# BOWIE_IMU.net
KiCad netlist of a schematic drawn in Altium Designer
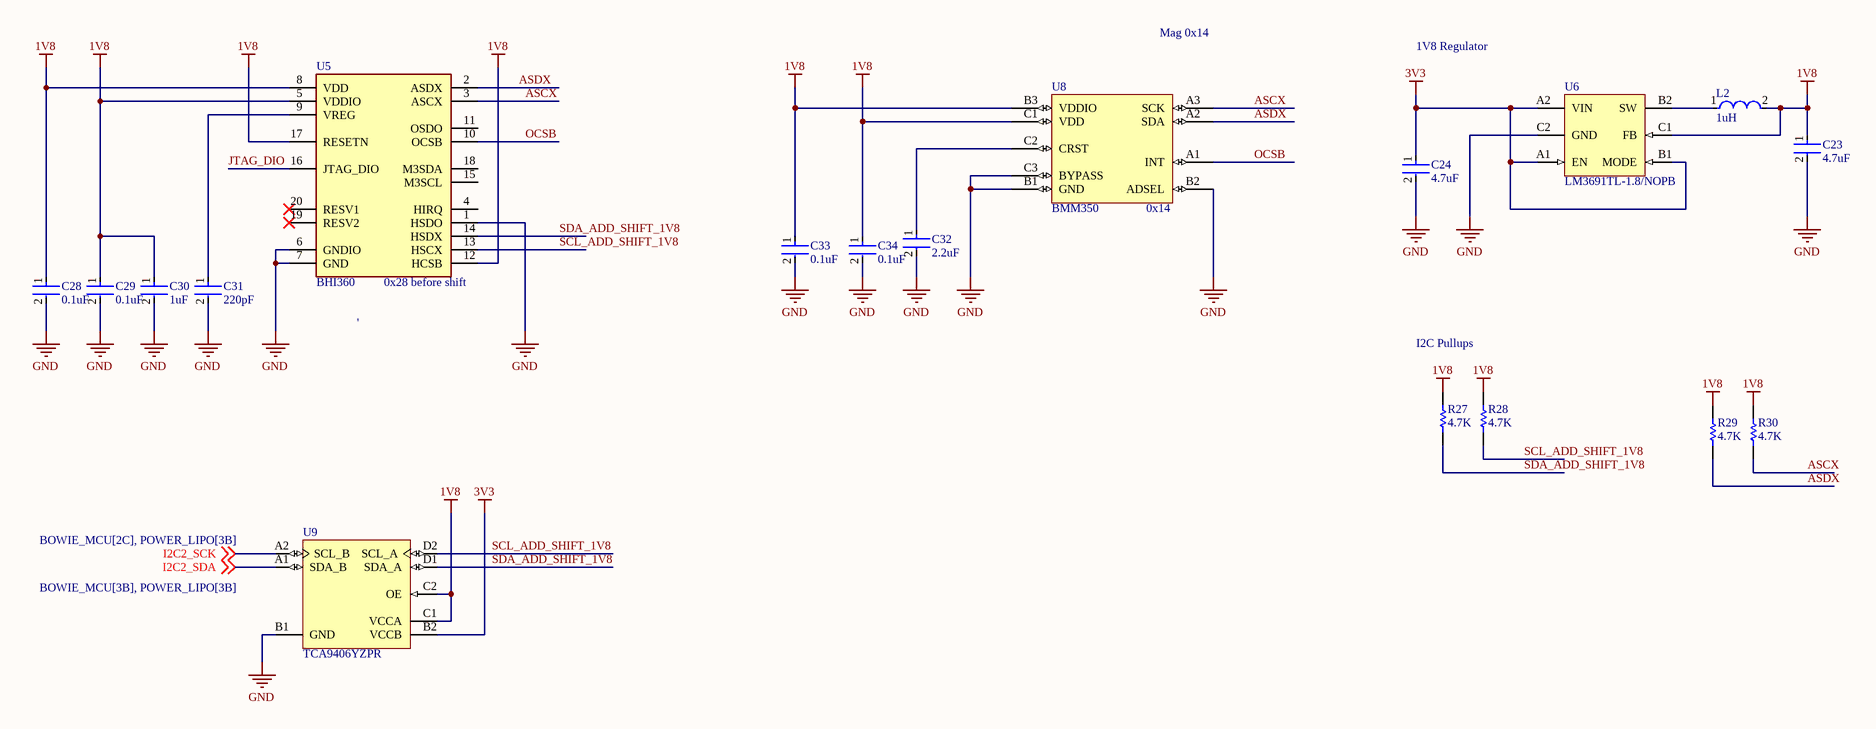
[diagram p0: BOWIE_IMU.SchDoc]

(export (version "E")
  (design (tool "Eeschema 10.0.6"))
  (components
    (comp (ref "C23")
      (value "4.7uF")
      (footprint "FP-CL828-IPC_C")
      (description "Cap Ceramic 4.7uF 10V X5R ±10% SMD 0402 +85°C Paper T/R")
      (fields (field (name "TOLERANCE") "10%"))
      (libsource (lib "Altium Content Vault") (part "b4654b650e69147ec39a6b967a45e02"))
    )
    (comp (ref "C24")
      (value "4.7uF")
      (footprint "FP-CL828-IPC_C")
      (description "Cap Ceramic 4.7uF 10V X5R ±10% SMD 0402 +85°C Paper T/R")
      (fields (field (name "TOLERANCE") "10%"))
      (libsource (lib "Altium Content Vault") (part "b4654b650e69147ec39a6b967a45e02"))
    )
    (comp (ref "C28")
      (value "0.1uF")
      (footprint "FP-GRM033-0_03-IPC_C")
      (description "Chip Multilayer Ceramic Capacitors for General Purpose, 0201, 0.10uF, X5R, 15%, 10%, 10V")
      (fields (field (name "TOLERANCE") "10%") (field (name "VOLTAGE") "10V"))
      (libsource (lib "Altium Content Vault") (part "b4654b650e69147ec39a6b967a45e02"))
    )
    (comp (ref "C29")
      (value "0.1uF")
      (footprint "FP-GRM033-0_03-IPC_C")
      (description "Chip Multilayer Ceramic Capacitors for General Purpose, 0201, 0.10uF, X5R, 15%, 10%, 10V")
      (fields (field (name "TOLERANCE") "10%") (field (name "VOLTAGE") "10V"))
      (libsource (lib "Altium Content Vault") (part "b4654b650e69147ec39a6b967a45e02"))
    )
    (comp (ref "C30")
      (value "1uF")
      (footprint "FP-GRM033-0_05-e01_0_2-IPC_C")
      (description "Chip Multilayer Ceramic Capacitors for General Purpose, 0201, 1.0uF, X5R, 15%, 20%, 4V")
      (fields (field (name "TOLERANCE") "20%"))
      (libsource (lib "Altium Content Vault") (part "02cd4be3c70576c341d710602a673aa"))
    )
    (comp (ref "C31")
      (value "220pF")
      (footprint "FP-GRM033-0_03-IPC_C")
      (description "Chip Multilayer Ceramic Capacitors for General Purpose, 0201, 220pF, X7R, 15%, 10%, 16V")
      (fields (field (name "TOLERANCE") "10%"))
      (libsource (lib "Altium Content Vault") (part "b4654b650e69147ec39a6b967a45e02"))
    )
    (comp (ref "C32")
      (value "2.2uF")
      (footprint "FP-GRM033-0_09-IPC_B")
      (description "Chip Multilayer Ceramic Capacitors for General Purpose, 0201, 2.2uF, X5R, 15%, 10%, 10V")
      (fields (field (name "TOLERANCE") "10%"))
      (libsource (lib "Altium Content Vault") (part "02cd4be3c70576c341d710602a673aa"))
    )
    (comp (ref "C33")
      (value "0.1uF")
      (footprint "FP-GRM033-0_03-IPC_C")
      (description "Chip Multilayer Ceramic Capacitors for General Purpose, 0201, 0.10uF, X5R, 15%, 10%, 10V")
      (fields (field (name "TOLERANCE") "10%") (field (name "VOLTAGE") "10V"))
      (libsource (lib "Altium Content Vault") (part "b4654b650e69147ec39a6b967a45e02"))
    )
    (comp (ref "C34")
      (value "0.1uF")
      (footprint "FP-GRM033-0_03-IPC_C")
      (description "Chip Multilayer Ceramic Capacitors for General Purpose, 0201, 0.10uF, X5R, 15%, 10%, 10V")
      (fields (field (name "TOLERANCE") "10%") (field (name "VOLTAGE") "10V"))
      (libsource (lib "Altium Content Vault") (part "b4654b650e69147ec39a6b967a45e02"))
    )
    (comp (ref "L2")
      (value "1uH")
      (footprint "FP-DFE18SAN_E0-MFG")
      (description "FIXED IND 1UH 1.6A 144 MOHM SMD")
      (fields (field (name "TOLERANCE") "20%"))
      (libsource (lib "Altium Content Vault") (part "725321dda6339637d4d059423bc1c3c"))
    )
    (comp (ref "R27")
      (value "4.7K")
      (footprint "RESC0603X26X15NL03T05")
      (fields (field (name "PART NUMBER") "ERJ-1GEF4701C") (field (name "MANUFACTURER") "Panasonic"))
      (libsource (lib "Altium Content Vault") (part "RES"))
    )
    (comp (ref "R28")
      (value "4.7K")
      (footprint "RESC0603X26X15NL03T05")
      (fields (field (name "PART NUMBER") "ERJ-1GEF4701C") (field (name "MANUFACTURER") "Panasonic"))
      (libsource (lib "Altium Content Vault") (part "RES"))
    )
    (comp (ref "R29")
      (value "4.7K")
      (footprint "RESC0603X26X15NL03T05")
      (fields (field (name "PART NUMBER") "ERJ-1GEF4701C") (field (name "MANUFACTURER") "Panasonic"))
      (libsource (lib "Altium Content Vault") (part "RES"))
    )
    (comp (ref "R30")
      (value "4.7K")
      (footprint "RESC0603X26X15NL03T05")
      (fields (field (name "PART NUMBER") "ERJ-1GEF4701C") (field (name "MANUFACTURER") "Panasonic"))
      (libsource (lib "Altium Content Vault") (part "RES"))
    )
    (comp (ref "U5")
      (value "BHI360")
      (footprint "BHI360")
      (fields (field (name "MOUSER PART NUMBER") "262-BHI360"))
      (libsource (lib "BHI360") (part "BHI360"))
    )
    (comp (ref "U6")
      (value "LM3691TL-1.8/NOPB")
      (footprint "YZR0006APAF")
      (fields (field (name "MANUFACTURER") "Texas Instruments"))
      (libsource (lib "Altium Content Vault") (part "PM-DCDC-LM3691-6"))
    )
    (comp (ref "U8") (value "BMM350") (footprint "BMM350") (libsource (lib "bmm350") (part "BMM350")))
    (comp (ref "U9")
      (value "TCA9406YZPR")
      (footprint "YZP0008ADAD")
      (fields (field (name "MANUFACTURER") "Texas Instruments"))
      (libsource (lib "Altium Content Vault") (part "TI-TCA9406-DSBGA_YZP-8"))
    )
  )
  (nets
    (net (code "1") (name "/ASCX") (class "Default")
      (node (ref "R30") (pin "1") (pinfunction "1_1") (pintype "passive"))
      (node (ref "U5") (pin "3") (pinfunction "ASCX_3") (pintype "passive"))
      (node (ref "U8") (pin "A3") (pinfunction "SCK_A3") (pintype "bidirectional"))
    )
    (net (code "2") (name "/ASDX") (class "Default")
      (node (ref "R29") (pin "1") (pinfunction "1_1") (pintype "passive"))
      (node (ref "U5") (pin "2") (pinfunction "ASDX_2") (pintype "passive"))
      (node (ref "U8") (pin "A2") (pinfunction "SDA_A2") (pintype "bidirectional"))
    )
    (net (code "3") (name "/JTAG_DIO") (class "Default")
      (node (ref "U5") (pin "16") (pinfunction "JTAG_DIO_16") (pintype "passive"))
    )
    (net (code "4") (name "/OCSB") (class "Default")
      (node (ref "U5") (pin "10") (pinfunction "OCSB_10") (pintype "passive"))
      (node (ref "U8") (pin "A1") (pinfunction "INT_A1") (pintype "bidirectional"))
    )
    (net (code "5") (name "/SCL_ADD_SHIFT_1V8") (class "Default")
      (node (ref "R28") (pin "1") (pinfunction "1_1") (pintype "passive"))
      (node (ref "U5") (pin "13") (pinfunction "HSCX_13") (pintype "passive"))
      (node (ref "U9") (pin "D2") (pinfunction "SCL_A_D2") (pintype "bidirectional"))
    )
    (net (code "6") (name "/SDA_ADD_SHIFT_1V8") (class "Default")
      (node (ref "R27") (pin "1") (pinfunction "1_1") (pintype "passive"))
      (node (ref "U5") (pin "14") (pinfunction "HSDX_14") (pintype "passive"))
      (node (ref "U9") (pin "D1") (pinfunction "SDA_A_D1") (pintype "bidirectional"))
    )
    (net (code "7") (name "1V8") (class "Default")
      (node (ref "C23") (pin "1") (pinfunction "1_1") (pintype "passive"))
      (node (ref "C28") (pin "1") (pinfunction "1_1") (pintype "passive"))
      (node (ref "C29") (pin "1") (pinfunction "1_1") (pintype "passive"))
      (node (ref "C30") (pin "1") (pinfunction "1_1") (pintype "passive"))
      (node (ref "C33") (pin "1") (pinfunction "1_1") (pintype "passive"))
      (node (ref "C34") (pin "1") (pinfunction "1_1") (pintype "passive"))
      (node (ref "L2") (pin "2") (pinfunction "2_2") (pintype "passive"))
      (node (ref "R27") (pin "2") (pinfunction "2_2") (pintype "passive"))
      (node (ref "R28") (pin "2") (pinfunction "2_2") (pintype "passive"))
      (node (ref "R29") (pin "2") (pinfunction "2_2") (pintype "passive"))
      (node (ref "R30") (pin "2") (pinfunction "2_2") (pintype "passive"))
      (node (ref "U5") (pin "12") (pinfunction "HCSB_12") (pintype "passive"))
      (node (ref "U5") (pin "17") (pinfunction "RESETN_17") (pintype "passive"))
      (node (ref "U5") (pin "5") (pinfunction "VDDIO_5") (pintype "passive"))
      (node (ref "U5") (pin "8") (pinfunction "VDD_8") (pintype "passive"))
      (node (ref "U6") (pin "C1") (pinfunction "FB_C1") (pintype "input"))
      (node (ref "U8") (pin "B3") (pinfunction "VDDIO_B3") (pintype "bidirectional"))
      (node (ref "U8") (pin "C1") (pinfunction "VDD_C1") (pintype "bidirectional"))
      (node (ref "U9") (pin "C1") (pinfunction "VCCA_C1") (pintype "power_in"))
      (node (ref "U9") (pin "C2") (pinfunction "OE_C2") (pintype "input"))
    )
    (net (code "8") (name "3V3") (class "Default")
      (node (ref "C24") (pin "1") (pinfunction "1_1") (pintype "passive"))
      (node (ref "U6") (pin "A1") (pinfunction "EN_A1") (pintype "input"))
      (node (ref "U6") (pin "A2") (pinfunction "VIN_A2") (pintype "power_in"))
      (node (ref "U6") (pin "B1") (pinfunction "MODE_B1") (pintype "input"))
      (node (ref "U9") (pin "B2") (pinfunction "VCCB_B2") (pintype "power_in"))
    )
    (net (code "9") (name "GND") (class "Default")
      (node (ref "C23") (pin "2") (pinfunction "2_2") (pintype "passive"))
      (node (ref "C24") (pin "2") (pinfunction "2_2") (pintype "passive"))
      (node (ref "C28") (pin "2") (pinfunction "2_2") (pintype "passive"))
      (node (ref "C29") (pin "2") (pinfunction "2_2") (pintype "passive"))
      (node (ref "C30") (pin "2") (pinfunction "2_2") (pintype "passive"))
      (node (ref "C31") (pin "2") (pinfunction "2_2") (pintype "passive"))
      (node (ref "C32") (pin "2") (pinfunction "2_2") (pintype "passive"))
      (node (ref "C33") (pin "2") (pinfunction "2_2") (pintype "passive"))
      (node (ref "C34") (pin "2") (pinfunction "2_2") (pintype "passive"))
      (node (ref "U5") (pin "1") (pinfunction "HSDO_1") (pintype "passive"))
      (node (ref "U5") (pin "6") (pinfunction "GNDIO_6") (pintype "passive"))
      (node (ref "U5") (pin "7") (pinfunction "GND_7") (pintype "passive"))
      (node (ref "U6") (pin "C2") (pinfunction "GND_C2") (pintype "power_in"))
      (node (ref "U8") (pin "B1") (pinfunction "GND_B1") (pintype "bidirectional"))
      (node (ref "U8") (pin "B2") (pinfunction "ADSEL_B2") (pintype "bidirectional"))
      (node (ref "U8") (pin "C3") (pinfunction "BYPASS_C3") (pintype "bidirectional"))
      (node (ref "U9") (pin "B1") (pinfunction "GND_B1") (pintype "power_in"))
    )
    (net (code "10") (name "I2C2_SCK") (class "Default")
      (node (ref "U9") (pin "A2") (pinfunction "SCL_B_A2") (pintype "bidirectional"))
    )
    (net (code "11") (name "I2C2_SDA") (class "Default")
      (node (ref "U9") (pin "A1") (pinfunction "SDA_B_A1") (pintype "bidirectional"))
    )
    (net (code "12") (name "Net-(U5-VREG)") (class "Default")
      (node (ref "C31") (pin "1") (pinfunction "1_1") (pintype "passive"))
      (node (ref "U5") (pin "9") (pinfunction "VREG_9") (pintype "passive"))
    )
    (net (code "13") (name "Net-(U6-SW)") (class "Default")
      (node (ref "L2") (pin "1") (pinfunction "1_1") (pintype "passive"))
      (node (ref "U6") (pin "B2") (pinfunction "SW_B2") (pintype "power_in"))
    )
    (net (code "14") (name "Net-(U8-CRST)") (class "Default")
      (node (ref "C32") (pin "1") (pinfunction "1_1") (pintype "passive"))
      (node (ref "U8") (pin "C2") (pinfunction "CRST_C2") (pintype "bidirectional"))
    )
    (net (code "15") (name "unconnected-(U5-HIRQ-Pad4)") (class "Default")
      (node (ref "U5") (pin "4") (pinfunction "HIRQ_4") (pintype "passive"))
    )
    (net (code "16") (name "unconnected-(U5-M3SCL-Pad15)") (class "Default")
      (node (ref "U5") (pin "15") (pinfunction "M3SCL_15") (pintype "passive"))
    )
    (net (code "17") (name "unconnected-(U5-M3SDA-Pad18)") (class "Default")
      (node (ref "U5") (pin "18") (pinfunction "M3SDA_18") (pintype "passive"))
    )
    (net (code "18") (name "unconnected-(U5-OSDO-Pad11)") (class "Default")
      (node (ref "U5") (pin "11") (pinfunction "OSDO_11") (pintype "passive"))
    )
    (net (code "19") (name "unconnected-(U5-RESV1-Pad20)") (class "Default")
      (node (ref "U5") (pin "20") (pinfunction "RESV1_20") (pintype "passive+no_connect"))
    )
    (net (code "20") (name "unconnected-(U5-RESV2-Pad19)") (class "Default")
      (node (ref "U5") (pin "19") (pinfunction "RESV2_19") (pintype "passive+no_connect"))
    )
  )
)
